# POWER.net
KiCad netlist of a schematic drawn in Altium Designer
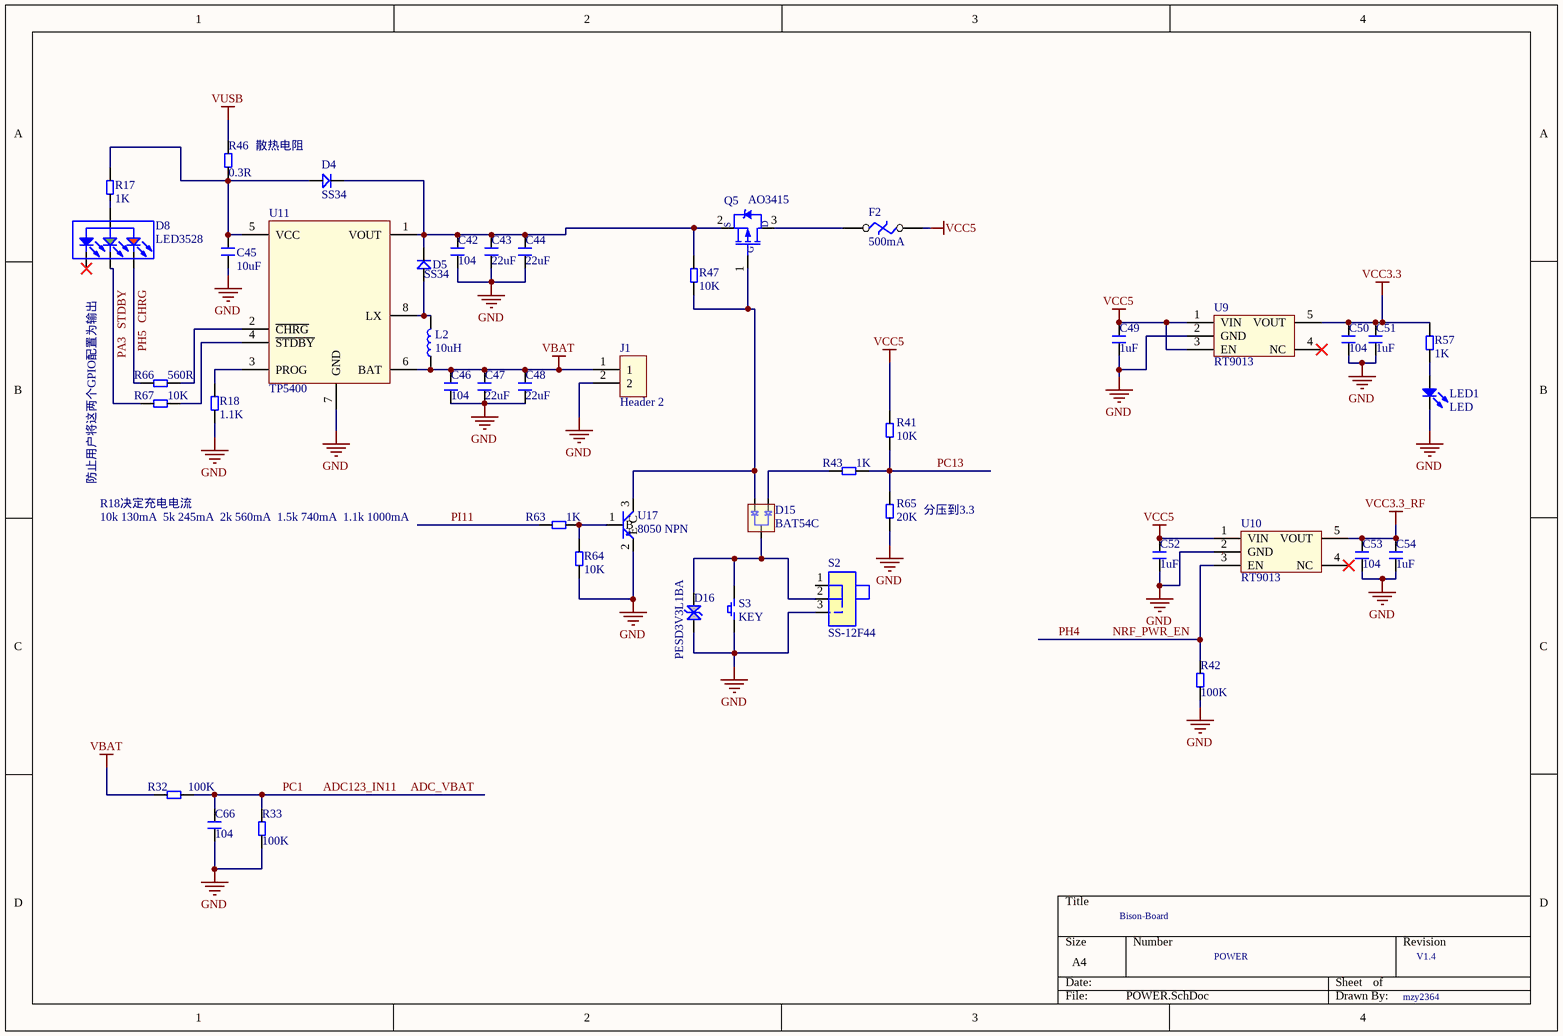
[diagram p0: POWER.SchDoc]

(export (version "E")
  (design (tool "Eeschema 10.0.6"))
  (components
    (comp (ref "C42") (value "104") (footprint "C 0603") (libsource (lib "Bison-Board") (part "CAP")))
    (comp (ref "C43") (value "22uF") (footprint "C 0805") (libsource (lib "Bison-Board") (part "CAP")))
    (comp (ref "C44") (value "22uF") (footprint "C 0805") (libsource (lib "Bison-Board") (part "CAP")))
    (comp (ref "C45") (value "10uF") (footprint "C 0805") (libsource (lib "Bison-Board") (part "CAP")))
    (comp (ref "C46") (value "104") (footprint "C 0603") (libsource (lib "Bison-Board") (part "CAP")))
    (comp (ref "C47") (value "22uF") (footprint "C 0805") (libsource (lib "Bison-Board") (part "CAP")))
    (comp (ref "C48") (value "22uF") (footprint "C 0805") (libsource (lib "Bison-Board") (part "CAP")))
    (comp (ref "C49") (value "1uF") (footprint "C 0603") (libsource (lib "Bison-Board") (part "CAP")))
    (comp (ref "C50") (value "104") (footprint "C 0603") (libsource (lib "Bison-Board") (part "CAP")))
    (comp (ref "C51") (value "1uF") (footprint "C 0603") (libsource (lib "Bison-Board") (part "CAP")))
    (comp (ref "C52") (value "1uF") (footprint "C 0603") (libsource (lib "Bison-Board") (part "CAP")))
    (comp (ref "C53") (value "104") (footprint "C 0603") (libsource (lib "Bison-Board") (part "CAP")))
    (comp (ref "C54") (value "1uF") (footprint "C 0603") (libsource (lib "Bison-Board") (part "CAP")))
    (comp (ref "C66") (value "104") (footprint "C 0603") (libsource (lib "Bison-Board") (part "CAP")))
    (comp (ref "D4") (value "SS34") (footprint "SMA") (libsource (lib "Bison-Board") (part "Diode")))
    (comp (ref "D5") (value "SS34") (footprint "SMA") (libsource (lib "Bison-Board") (part "Diode")))
    (comp (ref "D8")
      (value "LED3528")
      (footprint "LED3528-4PIN")
      (libsource (lib "squ-guiboard") (part "LED3528"))
    )
    (comp (ref "D15") (value "BAT54C") (footprint "SOT23-3") (libsource (lib "Bison-Board") (part "BAT54C")))
    (comp (ref "D16")
      (value "PESD3V3L1BA")
      (footprint "SOD323")
      (description "双向TVS")
      (libsource (lib "Bison-Board") (part "D Schottky1"))
    )
    (comp (ref "F2")
      (value "500mA")
      (footprint "F 0805")
      (description "熔断开关")
      (libsource (lib "Bison-Board") (part "F"))
    )
    (comp (ref "J1")
      (value "Header 2")
      (footprint "XH2.54-WS-2P")
      (libsource (lib "Bison-Board") (part "Header 2"))
    )
    (comp (ref "L2") (value "10uH") (footprint "L_SMNR4030") (libsource (lib "squ-guiboard") (part "L")))
    (comp (ref "LED1") (value "LED") (footprint "LED0603") (libsource (lib "squ-guiboard") (part "LED")))
    (comp (ref "Q5") (value "AO3415") (footprint "SOT23-3") (libsource (lib "squ-guiboard") (part "PMOS-2")))
    (comp (ref "R17") (value "1K") (footprint "R 0603") (libsource (lib "Bison-Board") (part "RES")))
    (comp (ref "R18") (value "1.1K") (footprint "R 0603") (libsource (lib "Bison-Board") (part "RES")))
    (comp (ref "R32") (value "100K") (footprint "R 0603") (libsource (lib "Bison-Board") (part "RES")))
    (comp (ref "R33") (value "100K") (footprint "R 0603") (libsource (lib "Bison-Board") (part "RES")))
    (comp (ref "R41") (value "10K") (footprint "R 0603") (libsource (lib "Bison-Board") (part "RES")))
    (comp (ref "R42") (value "100K") (footprint "R 0603") (libsource (lib "squ-guiboard") (part "RES")))
    (comp (ref "R43") (value "1K") (footprint "R 0603") (libsource (lib "Bison-Board") (part "RES")))
    (comp (ref "R46") (value "0.3R") (footprint "R 0805") (libsource (lib "Bison-Board") (part "RES")))
    (comp (ref "R47") (value "10K") (footprint "R 0603") (libsource (lib "Bison-Board") (part "RES")))
    (comp (ref "R57") (value "1K") (footprint "R 0603") (libsource (lib "squ-guiboard") (part "RES")))
    (comp (ref "R63") (value "1K") (footprint "R 0603") (libsource (lib "Bison-Board") (part "RES")))
    (comp (ref "R64") (value "10K") (footprint "R 0603") (libsource (lib "Bison-Board") (part "RES")))
    (comp (ref "R65") (value "20K") (footprint "R 0603") (libsource (lib "Bison-Board") (part "RES")))
    (comp (ref "R66") (value "560R") (footprint "R 0603") (libsource (lib "Bison-Board") (part "RES")))
    (comp (ref "R67") (value "10K") (footprint "R 0603") (libsource (lib "Bison-Board") (part "RES")))
    (comp (ref "S2")
      (value "SS-12F44")
      (footprint "K3-1280S-L1")
      (libsource (lib "squ-guiboard") (part "SWITCH"))
    )
    (comp (ref "S3") (value "KEY") (footprint "KEY-TC-153") (libsource (lib "Bison-Board") (part "KEY")))
    (comp (ref "U9")
      (value "RT9013")
      (footprint "SOT23-5")
      (description "500mA低压差LDO")
      (libsource (lib "squ-guiboard") (part "RT9013"))
    )
    (comp (ref "U10")
      (value "RT9013")
      (footprint "SOT23-5")
      (description "500mA低压差LDO")
      (libsource (lib "squ-guiboard") (part "RT9013"))
    )
    (comp (ref "U11") (value "TP5400") (footprint "TP5410") (libsource (lib "Bison-Board") (part "TP5410")))
    (comp (ref "U17") (value "8050 NPN") (footprint "SOT23-3") (libsource (lib "squ-guiboard") (part "NPN")))
  )
  (nets
    (net (code "1") (name "/ADC123_IN11") (class "Default")
      (node (ref "C66") (pin "2") (pinfunction "2_2") (pintype "passive"))
      (node (ref "R32") (pin "1") (pintype "passive"))
      (node (ref "R33") (pin "1") (pintype "passive"))
    )
    (net (code "2") (name "/CHRG") (class "Default")
      (node (ref "D8") (pin "1") (pinfunction "R_1") (pintype "passive"))
      (node (ref "R66") (pin "2") (pintype "passive"))
    )
    (net (code "3") (name "/NRF_PWR_EN") (class "Default")
      (node (ref "R42") (pin "2") (pintype "passive"))
      (node (ref "U10") (pin "3") (pinfunction "EN_3") (pintype "passive"))
    )
    (net (code "4") (name "/PA3") (class "Default")
      (node (ref "D8") (pin "4") (pinfunction "G_4") (pintype "passive"))
      (node (ref "R67") (pin "2") (pintype "passive"))
    )
    (net (code "5") (name "/PC13") (class "Default")
      (node (ref "R41") (pin "2") (pintype "passive"))
      (node (ref "R43") (pin "1") (pintype "passive"))
      (node (ref "R65") (pin "1") (pintype "passive"))
    )
    (net (code "6") (name "/PI11") (class "Default") (node (ref "R63") (pin "2") (pintype "passive")))
    (net (code "7") (name "GND") (class "Default")
      (node (ref "C42") (pin "1") (pinfunction "1_1") (pintype "passive"))
      (node (ref "C43") (pin "1") (pinfunction "1_1") (pintype "passive"))
      (node (ref "C44") (pin "1") (pinfunction "1_1") (pintype "passive"))
      (node (ref "C45") (pin "1") (pinfunction "1_1") (pintype "passive"))
      (node (ref "C46") (pin "1") (pinfunction "1_1") (pintype "passive"))
      (node (ref "C47") (pin "1") (pinfunction "1_1") (pintype "passive"))
      (node (ref "C48") (pin "1") (pinfunction "1_1") (pintype "passive"))
      (node (ref "C49") (pin "1") (pinfunction "1_1") (pintype "passive"))
      (node (ref "C50") (pin "1") (pinfunction "1_1") (pintype "passive"))
      (node (ref "C51") (pin "1") (pinfunction "1_1") (pintype "passive"))
      (node (ref "C52") (pin "1") (pinfunction "1_1") (pintype "passive"))
      (node (ref "C53") (pin "1") (pinfunction "1_1") (pintype "passive"))
      (node (ref "C54") (pin "1") (pinfunction "1_1") (pintype "passive"))
      (node (ref "C66") (pin "1") (pinfunction "1_1") (pintype "passive"))
      (node (ref "D16") (pin "1") (pinfunction "1_1") (pintype "passive"))
      (node (ref "J1") (pin "2") (pinfunction "2_2") (pintype "passive"))
      (node (ref "LED1") (pin "2") (pinfunction "K_2") (pintype "passive"))
      (node (ref "R18") (pin "1") (pintype "passive"))
      (node (ref "R33") (pin "2") (pintype "passive"))
      (node (ref "R42") (pin "1") (pintype "passive"))
      (node (ref "R64") (pin "2") (pintype "passive"))
      (node (ref "R65") (pin "2") (pintype "passive"))
      (node (ref "S2") (pin "3") (pinfunction "3_3") (pintype "passive"))
      (node (ref "S3") (pin "1") (pinfunction "1_1") (pintype "passive"))
      (node (ref "U10") (pin "2") (pinfunction "GND_2") (pintype "passive"))
      (node (ref "U11") (pin "7") (pinfunction "GND_7") (pintype "passive"))
      (node (ref "U17") (pin "2") (pinfunction "E_2") (pintype "passive"))
      (node (ref "U9") (pin "2") (pinfunction "GND_2") (pintype "passive"))
    )
    (net (code "8") (name "Net-(D8-+)") (class "Default")
      (node (ref "D8") (pin "2") (pinfunction "+_2") (pintype "passive"))
      (node (ref "R17") (pin "1") (pintype "passive"))
    )
    (net (code "9") (name "Net-(D15-Pad1)") (class "Default")
      (node (ref "D15") (pin "1") (pinfunction "1_1") (pintype "passive"))
      (node (ref "R43") (pin "2") (pintype "passive"))
    )
    (net (code "10") (name "Net-(D15-Pad3)") (class "Default")
      (node (ref "D15") (pin "3") (pinfunction "3_3") (pintype "passive"))
      (node (ref "D16") (pin "2") (pinfunction "2_2") (pintype "passive"))
      (node (ref "S2") (pin "2") (pinfunction "2_2") (pintype "passive"))
      (node (ref "S3") (pin "2") (pinfunction "2_2") (pintype "passive"))
    )
    (net (code "11") (name "Net-(LED1-A)") (class "Default")
      (node (ref "LED1") (pin "1") (pinfunction "A_1") (pintype "passive"))
      (node (ref "R57") (pin "1") (pintype "passive"))
    )
    (net (code "12") (name "Net-(Q5-D)") (class "Default")
      (node (ref "F2") (pin "2") (pinfunction "2_2") (pintype "passive"))
      (node (ref "Q5") (pin "3") (pinfunction "D_3") (pintype "passive"))
    )
    (net (code "13") (name "Net-(Q5-G)") (class "Default")
      (node (ref "D15") (pin "2") (pinfunction "2_2") (pintype "passive"))
      (node (ref "Q5") (pin "1") (pinfunction "G_1") (pintype "passive"))
      (node (ref "R47") (pin "2") (pintype "passive"))
      (node (ref "U17") (pin "3") (pinfunction "C_3") (pintype "passive"))
    )
    (net (code "14") (name "Net-(Q5-S)") (class "Default")
      (node (ref "C42") (pin "2") (pinfunction "2_2") (pintype "passive"))
      (node (ref "C43") (pin "2") (pinfunction "2_2") (pintype "passive"))
      (node (ref "C44") (pin "2") (pinfunction "2_2") (pintype "passive"))
      (node (ref "D4") (pin "2") (pintype "passive"))
      (node (ref "D5") (pin "2") (pintype "passive"))
      (node (ref "Q5") (pin "2") (pinfunction "S_2") (pintype "passive"))
      (node (ref "R47") (pin "1") (pintype "passive"))
      (node (ref "U11") (pin "1") (pinfunction "VOUT_1") (pintype "passive"))
    )
    (net (code "15") (name "Net-(U11-LX)") (class "Default")
      (node (ref "D5") (pin "1") (pintype "passive"))
      (node (ref "L2") (pin "1") (pinfunction "1_1") (pintype "passive"))
      (node (ref "U11") (pin "8") (pinfunction "LX_8") (pintype "passive"))
    )
    (net (code "16") (name "Net-(U11-PROG)") (class "Default")
      (node (ref "R18") (pin "2") (pintype "passive"))
      (node (ref "U11") (pin "3") (pinfunction "PROG_3") (pintype "passive"))
    )
    (net (code "17") (name "Net-(U11-VCC)") (class "Default")
      (node (ref "C45") (pin "2") (pinfunction "2_2") (pintype "passive"))
      (node (ref "D4") (pin "1") (pintype "passive"))
      (node (ref "R17") (pin "2") (pintype "passive"))
      (node (ref "R46") (pin "1") (pintype "passive"))
      (node (ref "U11") (pin "5") (pinfunction "VCC_5") (pintype "passive"))
    )
    (net (code "18") (name "Net-(U11-~{CHRG})") (class "Default")
      (node (ref "R66") (pin "1") (pintype "passive"))
      (node (ref "U11") (pin "2") (pinfunction "~{CHRG}_2") (pintype "passive"))
    )
    (net (code "19") (name "Net-(U11-~{STDBY})") (class "Default")
      (node (ref "R67") (pin "1") (pintype "passive"))
      (node (ref "U11") (pin "4") (pinfunction "~{STDBY}_4") (pintype "passive"))
    )
    (net (code "20") (name "Net-(U17-B)") (class "Default")
      (node (ref "R63") (pin "1") (pintype "passive"))
      (node (ref "R64") (pin "1") (pintype "passive"))
      (node (ref "U17") (pin "1") (pinfunction "B_1") (pintype "passive"))
    )
    (net (code "21") (name "VBAT") (class "Default")
      (node (ref "C46") (pin "2") (pinfunction "2_2") (pintype "passive"))
      (node (ref "C47") (pin "2") (pinfunction "2_2") (pintype "passive"))
      (node (ref "C48") (pin "2") (pinfunction "2_2") (pintype "passive"))
      (node (ref "J1") (pin "1") (pinfunction "1_1") (pintype "passive"))
      (node (ref "L2") (pin "2") (pinfunction "2_2") (pintype "passive"))
      (node (ref "R32") (pin "2") (pintype "passive"))
      (node (ref "U11") (pin "6") (pinfunction "BAT_6") (pintype "passive"))
    )
    (net (code "22") (name "VCC3.3") (class "Default")
      (node (ref "C50") (pin "2") (pinfunction "2_2") (pintype "passive"))
      (node (ref "C51") (pin "2") (pinfunction "2_2") (pintype "passive"))
      (node (ref "R57") (pin "2") (pintype "passive"))
      (node (ref "U9") (pin "5") (pinfunction "VOUT_5") (pintype "passive"))
    )
    (net (code "23") (name "VCC3.3_RF") (class "Default")
      (node (ref "C53") (pin "2") (pinfunction "2_2") (pintype "passive"))
      (node (ref "C54") (pin "2") (pinfunction "2_2") (pintype "passive"))
      (node (ref "U10") (pin "5") (pinfunction "VOUT_5") (pintype "passive"))
    )
    (net (code "24") (name "VCC5") (class "Default")
      (node (ref "C49") (pin "2") (pinfunction "2_2") (pintype "passive"))
      (node (ref "C52") (pin "2") (pinfunction "2_2") (pintype "passive"))
      (node (ref "F2") (pin "1") (pinfunction "1_1") (pintype "passive"))
      (node (ref "R41") (pin "1") (pintype "passive"))
      (node (ref "U10") (pin "1") (pinfunction "VIN_1") (pintype "passive"))
      (node (ref "U9") (pin "1") (pinfunction "VIN_1") (pintype "passive"))
      (node (ref "U9") (pin "3") (pinfunction "EN_3") (pintype "passive"))
    )
    (net (code "25") (name "VUSB") (class "Default") (node (ref "R46") (pin "2") (pintype "passive")))
    (net (code "26") (name "unconnected-(D8-B-Pad3)") (class "Default")
      (node (ref "D8") (pin "3") (pinfunction "B_3") (pintype "passive+no_connect"))
    )
    (net (code "27") (name "unconnected-(S2-Pad1)") (class "Default")
      (node (ref "S2") (pin "1") (pinfunction "1_1") (pintype "passive"))
    )
    (net (code "28") (name "unconnected-(U9-NC-Pad4)") (class "Default")
      (node (ref "U9") (pin "4") (pinfunction "NC_4") (pintype "passive+no_connect"))
    )
    (net (code "29") (name "unconnected-(U10-NC-Pad4)") (class "Default")
      (node (ref "U10") (pin "4") (pinfunction "NC_4") (pintype "passive+no_connect"))
    )
  )
)
